# PIC12F675P_Breakout_Board.net
KiCad netlist of a schematic drawn in EAGLE
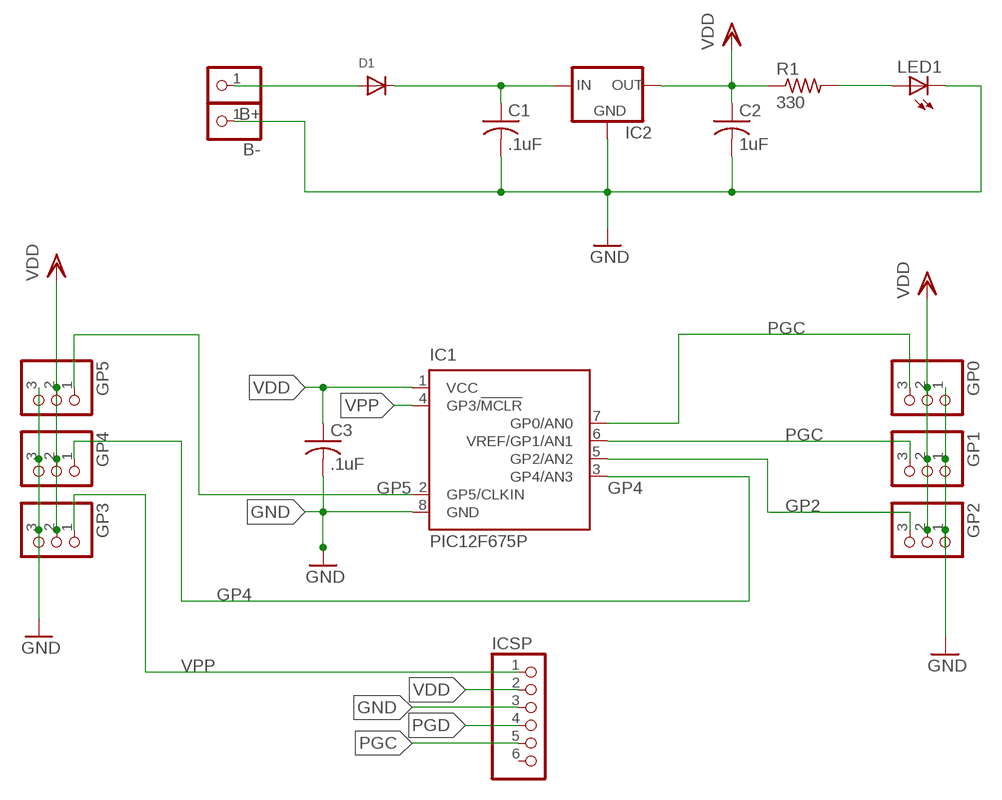
[diagram p0: schematic, sheet 1]

(export (version "E")
  (design (tool "Eeschema 10.0.6"))
  (components
    (comp (ref "B+")
      (value "PINHD-1X1")
      (footprint "eagle-import:1X01")
      (libsource (lib "eagle-import") (part "PINHD-1X1"))
    )
    (comp (ref "B-")
      (value "PINHD-1X1")
      (footprint "eagle-import:1X01")
      (libsource (lib "eagle-import") (part "PINHD-1X1"))
    )
    (comp (ref "C1")
      (value ".1uF")
      (footprint "eagle-import:C0805")
      (libsource (lib "eagle-import") (part "C-USC0805"))
    )
    (comp (ref "C2")
      (value "1uF")
      (footprint "eagle-import:C0805")
      (libsource (lib "eagle-import") (part "C-USC0805"))
    )
    (comp (ref "C3")
      (value ".1uF")
      (footprint "eagle-import:C0805")
      (libsource (lib "eagle-import") (part "C-USC0805"))
    )
    (comp (ref "D1")
      (value "DIODESMA")
      (footprint "eagle-import:SMADIODE")
      (libsource (lib "eagle-import") (part "DIODESMA"))
    )
    (comp (ref "GP0")
      (value "PINHD-1X3")
      (footprint "eagle-import:1X03")
      (libsource (lib "eagle-import") (part "PINHD-1X3"))
    )
    (comp (ref "GP1")
      (value "PINHD-1X3")
      (footprint "eagle-import:1X03")
      (libsource (lib "eagle-import") (part "PINHD-1X3"))
    )
    (comp (ref "GP2")
      (value "PINHD-1X3")
      (footprint "eagle-import:1X03")
      (libsource (lib "eagle-import") (part "PINHD-1X3"))
    )
    (comp (ref "GP3")
      (value "PINHD-1X3")
      (footprint "eagle-import:1X03")
      (libsource (lib "eagle-import") (part "PINHD-1X3"))
    )
    (comp (ref "GP4")
      (value "PINHD-1X3")
      (footprint "eagle-import:1X03")
      (libsource (lib "eagle-import") (part "PINHD-1X3"))
    )
    (comp (ref "GP5")
      (value "PINHD-1X3")
      (footprint "eagle-import:1X03")
      (libsource (lib "eagle-import") (part "PINHD-1X3"))
    )
    (comp (ref "IC1")
      (value "PIC12F675P")
      (footprint "eagle-import:DIL8")
      (fields (field (name "MF") "MICROCHIP") (field (name "MPN") "PIC12F675-E/P"))
      (libsource (lib "eagle-import") (part "PIC12F675P"))
    )
    (comp (ref "IC2")
      (value "78XXL")
      (footprint "eagle-import:78XXL")
      (libsource (lib "eagle-import") (part "78XXL"))
    )
    (comp (ref "ICSP")
      (value "PINHD-1X6")
      (footprint "eagle-import:1X06")
      (libsource (lib "eagle-import") (part "PINHD-1X6"))
    )
    (comp (ref "LED1")
      (value "LEDSML0805")
      (footprint "eagle-import:SML0805")
      (libsource (lib "eagle-import") (part "LEDSML0805"))
    )
    (comp (ref "R1")
      (value "330")
      (footprint "eagle-import:R0805")
      (libsource (lib "eagle-import") (part "R-US_R0805"))
    )
  )
  (nets
    (net (code "1") (name "/GP2") (class "Default")
      (node (ref "GP2") (pin "3") (pinfunction "3_3") (pintype "passive"))
      (node (ref "IC1") (pin "5") (pinfunction "GP2/AN2_5") (pintype "bidirectional"))
    )
    (net (code "2") (name "/GP4") (class "Default")
      (node (ref "GP4") (pin "1") (pinfunction "1_1") (pintype "passive"))
      (node (ref "IC1") (pin "3") (pinfunction "GP4/AN3_3") (pintype "bidirectional"))
    )
    (net (code "3") (name "/GP5") (class "Default")
      (node (ref "GP5") (pin "1") (pinfunction "1_1") (pintype "passive"))
      (node (ref "IC1") (pin "2") (pinfunction "GP5/CLKIN_2") (pintype "bidirectional"))
    )
    (net (code "4") (name "GND") (class "Default")
      (node (ref "B-") (pin "1") (pinfunction "1_1") (pintype "passive"))
      (node (ref "C1") (pin "2") (pinfunction "2_2") (pintype "passive"))
      (node (ref "C2") (pin "2") (pinfunction "2_2") (pintype "passive"))
      (node (ref "C3") (pin "2") (pinfunction "2_2") (pintype "passive"))
      (node (ref "GP0") (pin "1") (pinfunction "1_1") (pintype "passive"))
      (node (ref "GP1") (pin "1") (pinfunction "1_1") (pintype "passive"))
      (node (ref "GP2") (pin "1") (pinfunction "1_1") (pintype "passive"))
      (node (ref "GP3") (pin "3") (pinfunction "3_3") (pintype "passive"))
      (node (ref "GP4") (pin "3") (pinfunction "3_3") (pintype "passive"))
      (node (ref "GP5") (pin "3") (pinfunction "3_3") (pintype "passive"))
      (node (ref "IC1") (pin "8") (pinfunction "GND_8") (pintype "power_in"))
      (node (ref "IC2") (pin "GND") (pinfunction "GND_GND") (pintype "input"))
      (node (ref "ICSP") (pin "3") (pinfunction "3_3") (pintype "passive"))
      (node (ref "LED1") (pin "C") (pinfunction "C_C") (pintype "passive"))
    )
    (net (code "5") (name "Net-(B+-Pad1)") (class "Default")
      (node (ref "B+") (pin "1") (pinfunction "1_1") (pintype "passive"))
      (node (ref "D1") (pin "A") (pinfunction "A_A") (pintype "passive"))
    )
    (net (code "6") (name "Net-(C1-Pad1)") (class "Default")
      (node (ref "C1") (pin "1") (pinfunction "1_1") (pintype "passive"))
      (node (ref "D1") (pin "C") (pinfunction "C_C") (pintype "passive"))
      (node (ref "IC2") (pin "IN") (pinfunction "IN_IN") (pintype "input"))
    )
    (net (code "7") (name "Net-(LED1-PadA)") (class "Default")
      (node (ref "LED1") (pin "A") (pinfunction "A_A") (pintype "passive"))
      (node (ref "R1") (pin "2") (pinfunction "2_2") (pintype "passive"))
    )
    (net (code "8") (name "PGC") (class "Default")
      (node (ref "GP0") (pin "3") (pinfunction "3_3") (pintype "passive"))
      (node (ref "GP1") (pin "3") (pinfunction "3_3") (pintype "passive"))
      (node (ref "IC1") (pin "6") (pinfunction "VREF/GP1/AN1_6") (pintype "bidirectional"))
      (node (ref "IC1") (pin "7") (pinfunction "GP0/AN0_7") (pintype "bidirectional"))
      (node (ref "ICSP") (pin "5") (pinfunction "5_5") (pintype "passive"))
    )
    (net (code "9") (name "PGD") (class "Default")
      (node (ref "ICSP") (pin "4") (pinfunction "4_4") (pintype "passive"))
    )
    (net (code "10") (name "VDD") (class "Default")
      (node (ref "C2") (pin "1") (pinfunction "1_1") (pintype "passive"))
      (node (ref "C3") (pin "1") (pinfunction "1_1") (pintype "passive"))
      (node (ref "GP0") (pin "2") (pinfunction "2_2") (pintype "passive"))
      (node (ref "GP1") (pin "2") (pinfunction "2_2") (pintype "passive"))
      (node (ref "GP2") (pin "2") (pinfunction "2_2") (pintype "passive"))
      (node (ref "GP3") (pin "2") (pinfunction "2_2") (pintype "passive"))
      (node (ref "GP4") (pin "2") (pinfunction "2_2") (pintype "passive"))
      (node (ref "GP5") (pin "2") (pinfunction "2_2") (pintype "passive"))
      (node (ref "IC1") (pin "1") (pinfunction "VCC_1") (pintype "power_in"))
      (node (ref "IC2") (pin "OUT") (pinfunction "OUT_OUT") (pintype "passive"))
      (node (ref "ICSP") (pin "2") (pinfunction "2_2") (pintype "passive"))
      (node (ref "R1") (pin "1") (pinfunction "1_1") (pintype "passive"))
    )
    (net (code "11") (name "VPP") (class "Default")
      (node (ref "GP3") (pin "1") (pinfunction "1_1") (pintype "passive"))
      (node (ref "IC1") (pin "4") (pinfunction "GP3/~{MCLR}_4") (pintype "input"))
      (node (ref "ICSP") (pin "1") (pinfunction "1_1") (pintype "passive"))
    )
    (net (code "12") (name "unconnected-(ICSP-Pad6)") (class "Default")
      (node (ref "ICSP") (pin "6") (pinfunction "6_6") (pintype "passive"))
    )
  )
)
